# v1.net
KiCad netlist of a schematic drawn in EAGLE
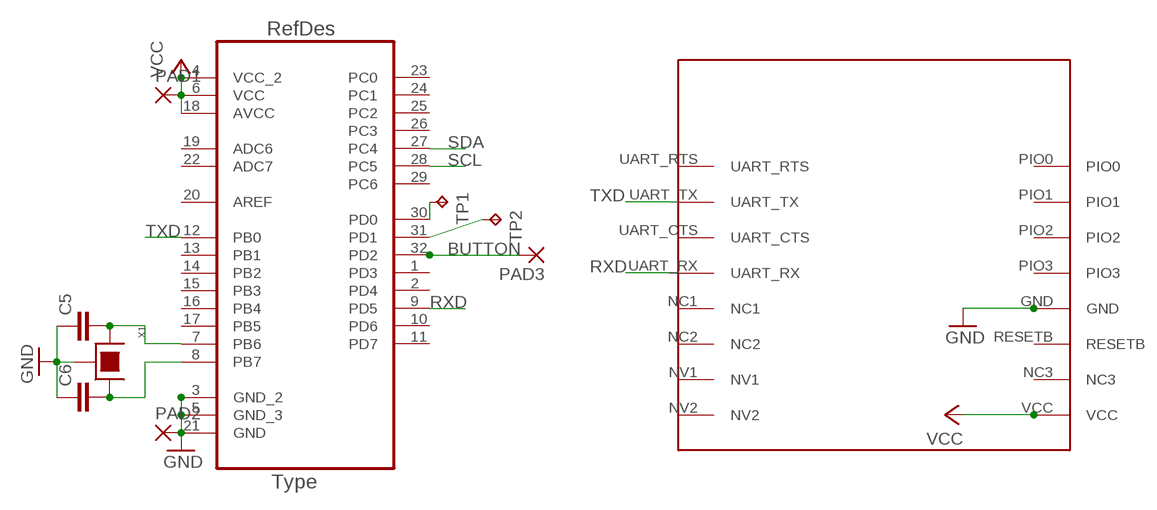
[diagram p0: schematic, sheet 1]
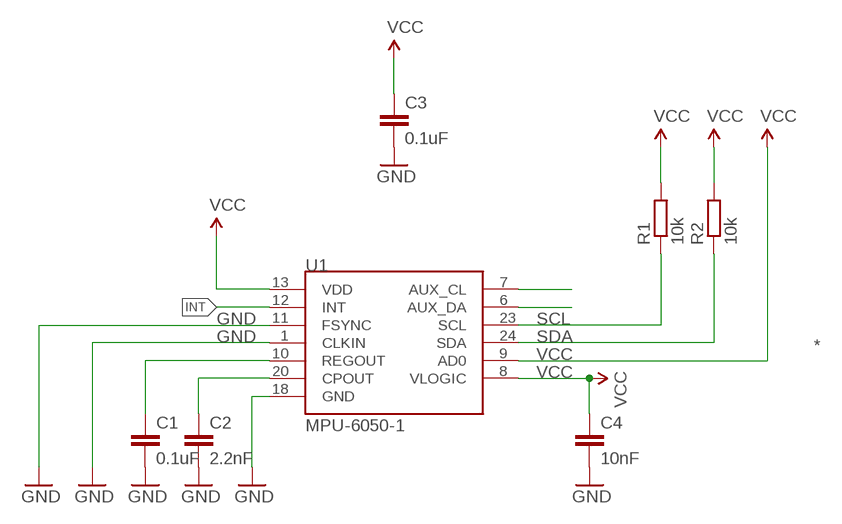
[diagram p1: schematic, sheet 2]

(export (version "E")
  (design (tool "Eeschema 10.0.6"))
  (components
    (comp (ref "C5")
      (value "C-EUC0402")
      (footprint "eagle-import:C0402")
      (libsource (lib "eagle-import") (part "C-EUC0402"))
    )
    (comp (ref "C6")
      (value "C-EUC0402")
      (footprint "eagle-import:C0402")
      (libsource (lib "eagle-import") (part "C-EUC0402"))
    )
    (comp (ref "PAD1")
      (value "SMD2")
      (footprint "eagle-import:SMD1,27-2,54")
      (libsource (lib "eagle-import") (part "SMD2"))
    )
    (comp (ref "PAD2")
      (value "SMD2")
      (footprint "eagle-import:SMD1,27-2,54")
      (libsource (lib "eagle-import") (part "SMD2"))
    )
    (comp (ref "PAD3")
      (value "SMD2")
      (footprint "eagle-import:SMD1,27-2,54")
      (libsource (lib "eagle-import") (part "SMD2"))
    )
    (comp (ref "TP1")
      (value "TPTP14R")
      (footprint "eagle-import:TP14R")
      (libsource (lib "eagle-import") (part "TPTP14R"))
    )
    (comp (ref "TP2")
      (value "TPTP14R")
      (footprint "eagle-import:TP14R")
      (libsource (lib "eagle-import") (part "TPTP14R"))
    )
    (comp (ref "U$1")
      (value "HM-11")
      (footprint "eagle-import:HM-11")
      (libsource (lib "eagle-import") (part "HM-11"))
    )
    (comp (ref "U2")
      (value "ATMEGA328P-AU")
      (footprint "eagle-import:QFP80P900X900X120-32N")
      (libsource (lib "eagle-import") (part "ATMEGA328P-AU"))
    )
    (comp (ref "X1")
      (value "SHIELDED_CRYSTAL_TSX-3225")
      (footprint "eagle-import:TSX-3225")
      (libsource (lib "eagle-import") (part "SHIELDED_CRYSTAL_TSX-3225"))
    )
    (comp (ref "C1")
      (value "0.1uF")
      (footprint "eagle-import:C0402")
      (libsource (lib "eagle-import") (part "C-EUC0402"))
    )
    (comp (ref "C2")
      (value "2.2nF")
      (footprint "eagle-import:C0402")
      (libsource (lib "eagle-import") (part "C-EUC0402"))
    )
    (comp (ref "C3")
      (value "0.1uF")
      (footprint "eagle-import:C0402")
      (libsource (lib "eagle-import") (part "C-EUC0402"))
    )
    (comp (ref "C4")
      (value "10nF")
      (footprint "eagle-import:C0402")
      (libsource (lib "eagle-import") (part "C-EUC0402"))
    )
    (comp (ref "R1")
      (value "10k")
      (footprint "eagle-import:R0402")
      (libsource (lib "eagle-import") (part "R-EU_R0402"))
    )
    (comp (ref "R2")
      (value "10k")
      (footprint "eagle-import:R0402")
      (libsource (lib "eagle-import") (part "R-EU_R0402"))
    )
    (comp (ref "U1")
      (value "MPU-6050-1")
      (footprint "eagle-import:QFN-24-4MM2")
      (libsource (lib "eagle-import") (part "MPU-6050-1"))
    )
  )
  (nets
    (net (code "1") (name "BUTTON") (class "Default")
      (node (ref "PAD3") (pin "1") (pinfunction "P_1") (pintype "passive"))
      (node (ref "U2") (pin "32") (pinfunction "PD2_32") (pintype "bidirectional"))
    )
    (net (code "2") (name "GND") (class "Default")
      (node (ref "C1") (pin "2") (pinfunction "2_2") (pintype "passive"))
      (node (ref "C2") (pin "2") (pinfunction "2_2") (pintype "passive"))
      (node (ref "C3") (pin "2") (pinfunction "2_2") (pintype "passive"))
      (node (ref "C4") (pin "2") (pinfunction "2_2") (pintype "passive"))
      (node (ref "C5") (pin "1") (pinfunction "1_1") (pintype "passive"))
      (node (ref "C6") (pin "1") (pinfunction "1_1") (pintype "passive"))
      (node (ref "PAD2") (pin "1") (pinfunction "P_1") (pintype "passive"))
      (node (ref "U$1") (pin "GND") (pinfunction "GND_GND") (pintype "bidirectional"))
      (node (ref "U1") (pin "1") (pinfunction "CLKIN_1") (pintype "bidirectional"))
      (node (ref "U1") (pin "11") (pinfunction "FSYNC_11") (pintype "bidirectional"))
      (node (ref "U1") (pin "18") (pinfunction "GND_18") (pintype "bidirectional"))
      (node (ref "U2") (pin "21") (pinfunction "GND_21") (pintype "passive"))
      (node (ref "U2") (pin "3") (pinfunction "GND_2_3") (pintype "passive"))
      (node (ref "U2") (pin "5") (pinfunction "GND_3_5") (pintype "passive"))
      (node (ref "X1") (pin "2") (pinfunction "P$3_2") (pintype "bidirectional"))
      (node (ref "X1") (pin "4") (pinfunction "P$3_4") (pintype "bidirectional"))
    )
    (net (code "3") (name "INT") (class "Default")
      (node (ref "U1") (pin "12") (pinfunction "INT_12") (pintype "bidirectional"))
    )
    (net (code "4") (name "Net-(U1-CPOUT)") (class "Default")
      (node (ref "C2") (pin "1") (pinfunction "1_1") (pintype "passive"))
      (node (ref "U1") (pin "20") (pinfunction "CPOUT_20") (pintype "bidirectional"))
    )
    (net (code "5") (name "Net-(U1-REGOUT)") (class "Default")
      (node (ref "C1") (pin "1") (pinfunction "1_1") (pintype "passive"))
      (node (ref "U1") (pin "10") (pinfunction "REGOUT_10") (pintype "bidirectional"))
    )
    (net (code "6") (name "Net-(U2-PB6)") (class "Default")
      (node (ref "C5") (pin "2") (pinfunction "2_2") (pintype "passive"))
      (node (ref "U2") (pin "7") (pinfunction "PB6_7") (pintype "bidirectional"))
      (node (ref "X1") (pin "1") (pinfunction "P$1_1") (pintype "bidirectional"))
    )
    (net (code "7") (name "Net-(U2-PB7)") (class "Default")
      (node (ref "C6") (pin "2") (pinfunction "2_2") (pintype "passive"))
      (node (ref "U2") (pin "8") (pinfunction "PB7_8") (pintype "bidirectional"))
      (node (ref "X1") (pin "3") (pinfunction "P$2_3") (pintype "bidirectional"))
    )
    (net (code "8") (name "Net-(U2-PD0)") (class "Default")
      (node (ref "TP1") (pin "TP") (pinfunction "TP_TP") (pintype "input"))
      (node (ref "U2") (pin "30") (pinfunction "PD0_30") (pintype "bidirectional"))
    )
    (net (code "9") (name "Net-(U2-PD1)") (class "Default")
      (node (ref "TP2") (pin "TP") (pinfunction "TP_TP") (pintype "input"))
      (node (ref "U2") (pin "31") (pinfunction "PD1_31") (pintype "bidirectional"))
    )
    (net (code "10") (name "RXD") (class "Default")
      (node (ref "U$1") (pin "UART_RX") (pinfunction "UART_RX_UART_RX") (pintype "bidirectional"))
      (node (ref "U2") (pin "9") (pinfunction "PD5_9") (pintype "bidirectional"))
    )
    (net (code "11") (name "SCL") (class "Default")
      (node (ref "R1") (pin "1") (pinfunction "1_1") (pintype "passive"))
      (node (ref "U1") (pin "23") (pinfunction "SCL_23") (pintype "bidirectional"))
      (node (ref "U2") (pin "28") (pinfunction "PC5_28") (pintype "bidirectional"))
    )
    (net (code "12") (name "SDA") (class "Default")
      (node (ref "R2") (pin "1") (pinfunction "1_1") (pintype "passive"))
      (node (ref "U1") (pin "24") (pinfunction "SDA_24") (pintype "bidirectional"))
      (node (ref "U2") (pin "27") (pinfunction "PC4_27") (pintype "bidirectional"))
    )
    (net (code "13") (name "TXD") (class "Default")
      (node (ref "U$1") (pin "UART_TX") (pinfunction "UART_TX_UART_TX") (pintype "bidirectional"))
      (node (ref "U2") (pin "12") (pinfunction "PB0_12") (pintype "bidirectional"))
    )
    (net (code "14") (name "VCC") (class "Default")
      (node (ref "C3") (pin "1") (pinfunction "1_1") (pintype "passive"))
      (node (ref "C4") (pin "1") (pinfunction "1_1") (pintype "passive"))
      (node (ref "PAD1") (pin "1") (pinfunction "P_1") (pintype "passive"))
      (node (ref "R1") (pin "2") (pinfunction "2_2") (pintype "passive"))
      (node (ref "R2") (pin "2") (pinfunction "2_2") (pintype "passive"))
      (node (ref "U$1") (pin "VCC") (pinfunction "VCC_VCC") (pintype "bidirectional"))
      (node (ref "U1") (pin "13") (pinfunction "VDD_13") (pintype "bidirectional"))
      (node (ref "U1") (pin "8") (pinfunction "VLOGIC_8") (pintype "bidirectional"))
      (node (ref "U1") (pin "9") (pinfunction "AD0_9") (pintype "bidirectional"))
      (node (ref "U2") (pin "18") (pinfunction "AVCC_18") (pintype "power_in"))
      (node (ref "U2") (pin "4") (pinfunction "VCC_2_4") (pintype "power_in"))
      (node (ref "U2") (pin "6") (pinfunction "VCC_6") (pintype "power_in"))
    )
    (net (code "15") (name "unconnected-(U$1-PadNC1)") (class "Default")
      (node (ref "U$1") (pin "NC1") (pinfunction "NC1_NC1") (pintype "bidirectional"))
    )
    (net (code "16") (name "unconnected-(U$1-PadNC2)") (class "Default")
      (node (ref "U$1") (pin "NC2") (pinfunction "NC2_NC2") (pintype "bidirectional"))
    )
    (net (code "17") (name "unconnected-(U$1-PadNC3)") (class "Default")
      (node (ref "U$1") (pin "NC3") (pinfunction "NC3_NC3") (pintype "bidirectional"))
    )
    (net (code "18") (name "unconnected-(U$1-PadNV1)") (class "Default")
      (node (ref "U$1") (pin "NV1") (pinfunction "NV1_NV1") (pintype "bidirectional"))
    )
    (net (code "19") (name "unconnected-(U$1-PadNV2)") (class "Default")
      (node (ref "U$1") (pin "NV2") (pinfunction "NV2_NV2") (pintype "bidirectional"))
    )
    (net (code "20") (name "unconnected-(U$1-PadPIO0)") (class "Default")
      (node (ref "U$1") (pin "PIO0") (pinfunction "PIO0_PIO0") (pintype "bidirectional"))
    )
    (net (code "21") (name "unconnected-(U$1-PadPIO1)") (class "Default")
      (node (ref "U$1") (pin "PIO1") (pinfunction "PIO1_PIO1") (pintype "bidirectional"))
    )
    (net (code "22") (name "unconnected-(U$1-PadPIO2)") (class "Default")
      (node (ref "U$1") (pin "PIO2") (pinfunction "PIO2_PIO2") (pintype "bidirectional"))
    )
    (net (code "23") (name "unconnected-(U$1-PadPIO3)") (class "Default")
      (node (ref "U$1") (pin "PIO3") (pinfunction "PIO3_PIO3") (pintype "bidirectional"))
    )
    (net (code "24") (name "unconnected-(U$1-PadRESETB)") (class "Default")
      (node (ref "U$1") (pin "RESETB") (pinfunction "RESETB_RESETB") (pintype "bidirectional"))
    )
    (net (code "25") (name "unconnected-(U$1-PadUART_CTS)") (class "Default")
      (node (ref "U$1") (pin "UART_CTS") (pinfunction "UART_CTS_UART_CTS") (pintype "bidirectional"))
    )
    (net (code "26") (name "unconnected-(U$1-PadUART_RTS)") (class "Default")
      (node (ref "U$1") (pin "UART_RTS") (pinfunction "UART_RTS_UART_RTS") (pintype "bidirectional"))
    )
    (net (code "27") (name "unconnected-(U1-AUX_CL-Pad7)") (class "Default")
      (node (ref "U1") (pin "7") (pinfunction "AUX_CL_7") (pintype "bidirectional"))
    )
    (net (code "28") (name "unconnected-(U1-AUX_DA-Pad6)") (class "Default")
      (node (ref "U1") (pin "6") (pinfunction "AUX_DA_6") (pintype "bidirectional"))
    )
    (net (code "29") (name "unconnected-(U2-ADC6-Pad19)") (class "Default")
      (node (ref "U2") (pin "19") (pinfunction "ADC6_19") (pintype "input"))
    )
    (net (code "30") (name "unconnected-(U2-ADC7-Pad22)") (class "Default")
      (node (ref "U2") (pin "22") (pinfunction "ADC7_22") (pintype "input"))
    )
    (net (code "31") (name "unconnected-(U2-AREF-Pad20)") (class "Default")
      (node (ref "U2") (pin "20") (pinfunction "AREF_20") (pintype "input"))
    )
    (net (code "32") (name "unconnected-(U2-PB1-Pad13)") (class "Default")
      (node (ref "U2") (pin "13") (pinfunction "PB1_13") (pintype "bidirectional"))
    )
    (net (code "33") (name "unconnected-(U2-PB2-Pad14)") (class "Default")
      (node (ref "U2") (pin "14") (pinfunction "PB2_14") (pintype "bidirectional"))
    )
    (net (code "34") (name "unconnected-(U2-PB3-Pad15)") (class "Default")
      (node (ref "U2") (pin "15") (pinfunction "PB3_15") (pintype "bidirectional"))
    )
    (net (code "35") (name "unconnected-(U2-PB4-Pad16)") (class "Default")
      (node (ref "U2") (pin "16") (pinfunction "PB4_16") (pintype "bidirectional"))
    )
    (net (code "36") (name "unconnected-(U2-PB5-Pad17)") (class "Default")
      (node (ref "U2") (pin "17") (pinfunction "PB5_17") (pintype "bidirectional"))
    )
    (net (code "37") (name "unconnected-(U2-PC0-Pad23)") (class "Default")
      (node (ref "U2") (pin "23") (pinfunction "PC0_23") (pintype "bidirectional"))
    )
    (net (code "38") (name "unconnected-(U2-PC1-Pad24)") (class "Default")
      (node (ref "U2") (pin "24") (pinfunction "PC1_24") (pintype "bidirectional"))
    )
    (net (code "39") (name "unconnected-(U2-PC2-Pad25)") (class "Default")
      (node (ref "U2") (pin "25") (pinfunction "PC2_25") (pintype "bidirectional"))
    )
    (net (code "40") (name "unconnected-(U2-PC3-Pad26)") (class "Default")
      (node (ref "U2") (pin "26") (pinfunction "PC3_26") (pintype "bidirectional"))
    )
    (net (code "41") (name "unconnected-(U2-PC6-Pad29)") (class "Default")
      (node (ref "U2") (pin "29") (pinfunction "PC6_29") (pintype "bidirectional"))
    )
    (net (code "42") (name "unconnected-(U2-PD3-Pad1)") (class "Default")
      (node (ref "U2") (pin "1") (pinfunction "PD3_1") (pintype "bidirectional"))
    )
    (net (code "43") (name "unconnected-(U2-PD4-Pad2)") (class "Default")
      (node (ref "U2") (pin "2") (pinfunction "PD4_2") (pintype "bidirectional"))
    )
    (net (code "44") (name "unconnected-(U2-PD6-Pad10)") (class "Default")
      (node (ref "U2") (pin "10") (pinfunction "PD6_10") (pintype "bidirectional"))
    )
    (net (code "45") (name "unconnected-(U2-PD7-Pad11)") (class "Default")
      (node (ref "U2") (pin "11") (pinfunction "PD7_11") (pintype "bidirectional"))
    )
  )
)
